# Networking.net
KiCad netlist of a schematic drawn in EAGLE
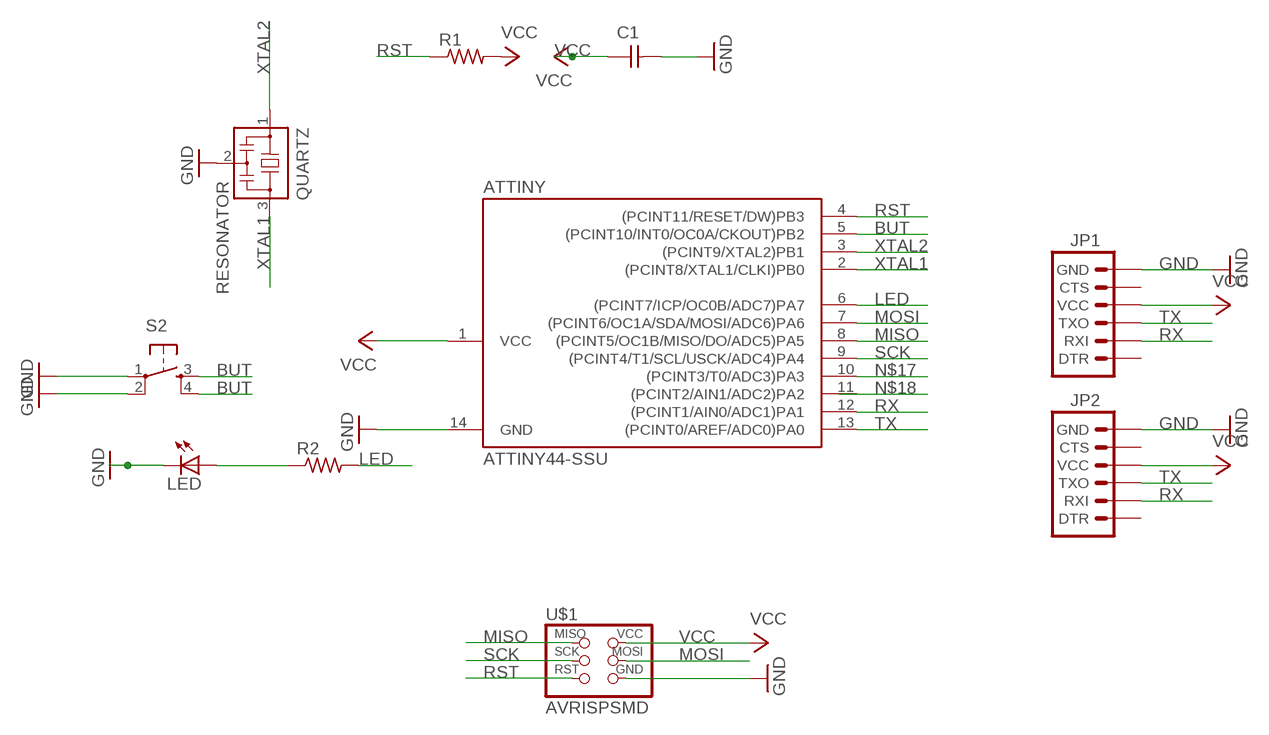
[diagram p0: schematic, sheet 1]

(export (version "E")
  (design (tool "Eeschema 10.0.6"))
  (components
    (comp (ref "ATTINY")
      (value "ATTINY44-SSU")
      (footprint "eagle-import:SOIC14")
      (libsource (lib "eagle-import") (part "ATTINY44-SSU"))
    )
    (comp (ref "C1")
      (value "UNPOLARIZED_CAPACITOR1206")
      (footprint "eagle-import:1206")
      (libsource (lib "eagle-import") (part "UNPOLARIZED_CAPACITOR1206"))
    )
    (comp (ref "JP1")
      (value "ARDUINO_SERIAL_PROGRAMLONGPADS")
      (footprint "eagle-import:1X06_LONGPADS")
      (libsource (lib "eagle-import") (part "ARDUINO_SERIAL_PROGRAMLONGPADS"))
    )
    (comp (ref "JP2")
      (value "ARDUINO_SERIAL_PROGRAMLONGPADS")
      (footprint "eagle-import:1X06_LONGPADS")
      (libsource (lib "eagle-import") (part "ARDUINO_SERIAL_PROGRAMLONGPADS"))
    )
    (comp (ref "LED")
      (value "LED1206")
      (footprint "eagle-import:1206")
      (libsource (lib "eagle-import") (part "LED1206"))
    )
    (comp (ref "QUARTZ")
      (value "RESONATOR")
      (footprint "eagle-import:EFOBM")
      (libsource (lib "eagle-import") (part "RESONATOR"))
    )
    (comp (ref "R1")
      (value "RESISTOR1206")
      (footprint "eagle-import:1206")
      (libsource (lib "eagle-import") (part "RESISTOR1206"))
    )
    (comp (ref "R2")
      (value "RESISTOR1206")
      (footprint "eagle-import:1206")
      (libsource (lib "eagle-import") (part "RESISTOR1206"))
    )
    (comp (ref "S2")
      (value "6MM_SWITCH6MM_SWITCH")
      (footprint "eagle-import:6MM_SWITCH")
      (libsource (lib "eagle-import") (part "6MM_SWITCH6MM_SWITCH"))
    )
    (comp (ref "U$1")
      (value "AVRISPSMD")
      (footprint "eagle-import:2X03SMD")
      (libsource (lib "eagle-import") (part "AVRISPSMD"))
    )
  )
  (nets
    (net (code "1") (name "/BUT") (class "Default")
      (node (ref "ATTINY") (pin "5") (pinfunction "(PCINT10/INT0/OC0A/CKOUT)PB2_5") (pintype "bidirectional"))
      (node (ref "S2") (pin "3") (pinfunction "S_3") (pintype "passive"))
      (node (ref "S2") (pin "4") (pinfunction "S1_4") (pintype "passive"))
    )
    (net (code "2") (name "/LED") (class "Default")
      (node (ref "ATTINY") (pin "6") (pinfunction "(PCINT7/ICP/OC0B/ADC7)PA7_6") (pintype "bidirectional"))
      (node (ref "R2") (pin "2") (pinfunction "2_2") (pintype "passive"))
    )
    (net (code "3") (name "/MISO") (class "Default")
      (node (ref "ATTINY") (pin "8") (pinfunction "(PCINT5/OC1B/MISO/DO/ADC5)PA5_8") (pintype "bidirectional"))
      (node (ref "U$1") (pin "1") (pinfunction "MISO_1") (pintype "passive"))
    )
    (net (code "4") (name "/MOSI") (class "Default")
      (node (ref "ATTINY") (pin "7") (pinfunction "(PCINT6/OC1A/SDA/MOSI/ADC6)PA6_7") (pintype "bidirectional"))
      (node (ref "U$1") (pin "4") (pinfunction "MOSI_4") (pintype "passive"))
    )
    (net (code "5") (name "/N$17") (class "Default")
      (node (ref "ATTINY") (pin "10") (pinfunction "(PCINT3/T0/ADC3)PA3_10") (pintype "bidirectional"))
    )
    (net (code "7") (name "/RST") (class "Default")
      (node (ref "ATTINY") (pin "4") (pinfunction "(PCINT11/RESET/DW)PB3_4") (pintype "bidirectional"))
      (node (ref "R1") (pin "1") (pinfunction "1_1") (pintype "passive"))
      (node (ref "U$1") (pin "5") (pinfunction "RST_5") (pintype "passive"))
    )
    (net (code "8") (name "/RX") (class "Default")
      (node (ref "ATTINY") (pin "12") (pinfunction "(PCINT1/AIN0/ADC1)PA1_12") (pintype "bidirectional"))
      (node (ref "JP1") (pin "2") (pinfunction "RXI_2") (pintype "passive"))
      (node (ref "JP2") (pin "2") (pinfunction "RXI_2") (pintype "passive"))
    )
    (net (code "9") (name "/SCK") (class "Default")
      (node (ref "ATTINY") (pin "9") (pinfunction "(PCINT4/T1/SCL/USCK/ADC4)PA4_9") (pintype "bidirectional"))
      (node (ref "U$1") (pin "3") (pinfunction "SCK_3") (pintype "passive"))
    )
    (net (code "10") (name "/TX") (class "Default")
      (node (ref "ATTINY") (pin "13") (pinfunction "(PCINT0/AREF/ADC0)PA0_13") (pintype "bidirectional"))
      (node (ref "JP1") (pin "3") (pinfunction "TXO_3") (pintype "passive"))
      (node (ref "JP2") (pin "3") (pinfunction "TXO_3") (pintype "passive"))
    )
    (net (code "11") (name "/XTAL1") (class "Default")
      (node (ref "ATTINY") (pin "2") (pinfunction "(PCINT8/XTAL1/CLKI)PB0_2") (pintype "bidirectional"))
      (node (ref "QUARTZ") (pin "3") (pinfunction "3_3") (pintype "passive"))
    )
    (net (code "12") (name "/XTAL2") (class "Default")
      (node (ref "ATTINY") (pin "3") (pinfunction "(PCINT9/XTAL2)PB1_3") (pintype "bidirectional"))
      (node (ref "QUARTZ") (pin "1") (pinfunction "1_1") (pintype "passive"))
    )
    (net (code "13") (name "GND") (class "Default")
      (node (ref "ATTINY") (pin "14") (pinfunction "GND_14") (pintype "power_in"))
      (node (ref "C1") (pin "2") (pinfunction "2_2") (pintype "passive"))
      (node (ref "JP1") (pin "6") (pinfunction "GND_6") (pintype "passive"))
      (node (ref "JP2") (pin "6") (pinfunction "GND_6") (pintype "passive"))
      (node (ref "LED") (pin "2") (pinfunction "C_2") (pintype "passive"))
      (node (ref "QUARTZ") (pin "2") (pinfunction "2_2") (pintype "passive"))
      (node (ref "S2") (pin "1") (pinfunction "P_1") (pintype "passive"))
      (node (ref "S2") (pin "2") (pinfunction "P1_2") (pintype "passive"))
      (node (ref "U$1") (pin "6") (pinfunction "GND_6") (pintype "passive"))
    )
    (net (code "14") (name "Net-(LED-A)") (class "Default")
      (node (ref "LED") (pin "1") (pinfunction "A_1") (pintype "passive"))
      (node (ref "R2") (pin "1") (pinfunction "1_1") (pintype "passive"))
    )
    (net (code "15") (name "VCC") (class "Default")
      (node (ref "ATTINY") (pin "1") (pinfunction "VCC_1") (pintype "power_in"))
      (node (ref "C1") (pin "1") (pinfunction "1_1") (pintype "passive"))
      (node (ref "JP1") (pin "4") (pinfunction "VCC_4") (pintype "passive"))
      (node (ref "JP2") (pin "4") (pinfunction "VCC_4") (pintype "passive"))
      (node (ref "R1") (pin "2") (pinfunction "2_2") (pintype "passive"))
      (node (ref "U$1") (pin "2") (pinfunction "VCC_2") (pintype "passive"))
    )
    (net (code "16") (name "unconnected-(ATTINY-(PCINT2{slash}AIN1{slash}ADC2)PA2-Pad11)") (class "Default")
      (node (ref "ATTINY") (pin "11") (pinfunction "(PCINT2/AIN1/ADC2)PA2_11") (pintype "bidirectional"))
    )
    (net (code "17") (name "unconnected-(JP1-CTS-Pad5)") (class "Default")
      (node (ref "JP1") (pin "5") (pinfunction "CTS_5") (pintype "passive"))
    )
    (net (code "18") (name "unconnected-(JP1-DTR-Pad1)") (class "Default")
      (node (ref "JP1") (pin "1") (pinfunction "DTR_1") (pintype "passive"))
    )
    (net (code "19") (name "unconnected-(JP2-CTS-Pad5)") (class "Default")
      (node (ref "JP2") (pin "5") (pinfunction "CTS_5") (pintype "passive"))
    )
    (net (code "20") (name "unconnected-(JP2-DTR-Pad1)") (class "Default")
      (node (ref "JP2") (pin "1") (pinfunction "DTR_1") (pintype "passive"))
    )
  )
)
